# voltage_regulator.net
KiCad netlist of a schematic drawn in Altium Designer
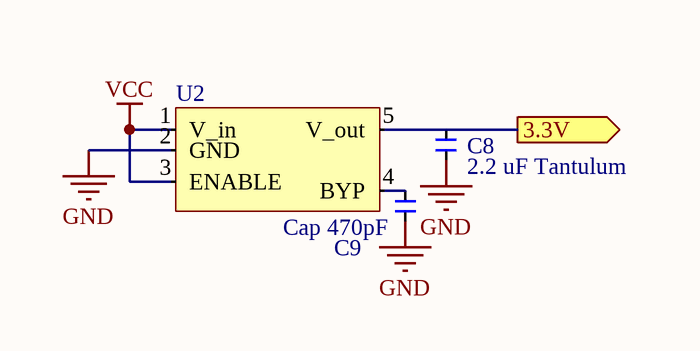
[diagram p0: voltage_regulator.SchDoc]

(export (version "E")
  (design (tool "Eeschema 10.0.6"))
  (components
    (comp (ref "C8")
      (value "2.2 uF Tantulum")
      (fields (field (name "TOLERANCE") "20%"))
      (libsource (lib "Schlib1") (part "2.2 uF Tantulum Cap"))
    )
    (comp (ref "C9") (value "Cap 470pF") (libsource (lib "Schlib1") (part "Cap 470pF")))
    (comp (ref "U2") (value "MIC5219 3.3 V") (libsource (lib "Schlib1") (part "MIC5219 3.3 V")))
  )
  (nets
    (net (code "1") (name "/3.3V") (class "Default")
      (node (ref "C8") (pin "4") (pinfunction "4_4") (pintype "passive"))
      (node (ref "U2") (pin "5") (pinfunction "V_out_5") (pintype "output"))
    )
    (net (code "2") (name "GND") (class "Default")
      (node (ref "C8") (pin "5") (pinfunction "5_5") (pintype "passive"))
      (node (ref "C9") (pin "5") (pinfunction "5_5") (pintype "passive"))
      (node (ref "U2") (pin "2") (pinfunction "GND_2") (pintype "power_in"))
    )
    (net (code "3") (name "Net-(U2-BYP)") (class "Default")
      (node (ref "C9") (pin "4") (pinfunction "4_4") (pintype "passive"))
      (node (ref "U2") (pin "4") (pinfunction "BYP_4") (pintype "power_in"))
    )
    (net (code "4") (name "VCC") (class "Default")
      (node (ref "U2") (pin "1") (pinfunction "V_in_1") (pintype "power_in"))
      (node (ref "U2") (pin "3") (pinfunction "ENABLE_3") (pintype "input"))
    )
  )
)
